# Sub_B_PCB.net
KiCad netlist of a schematic drawn in Altium Designer
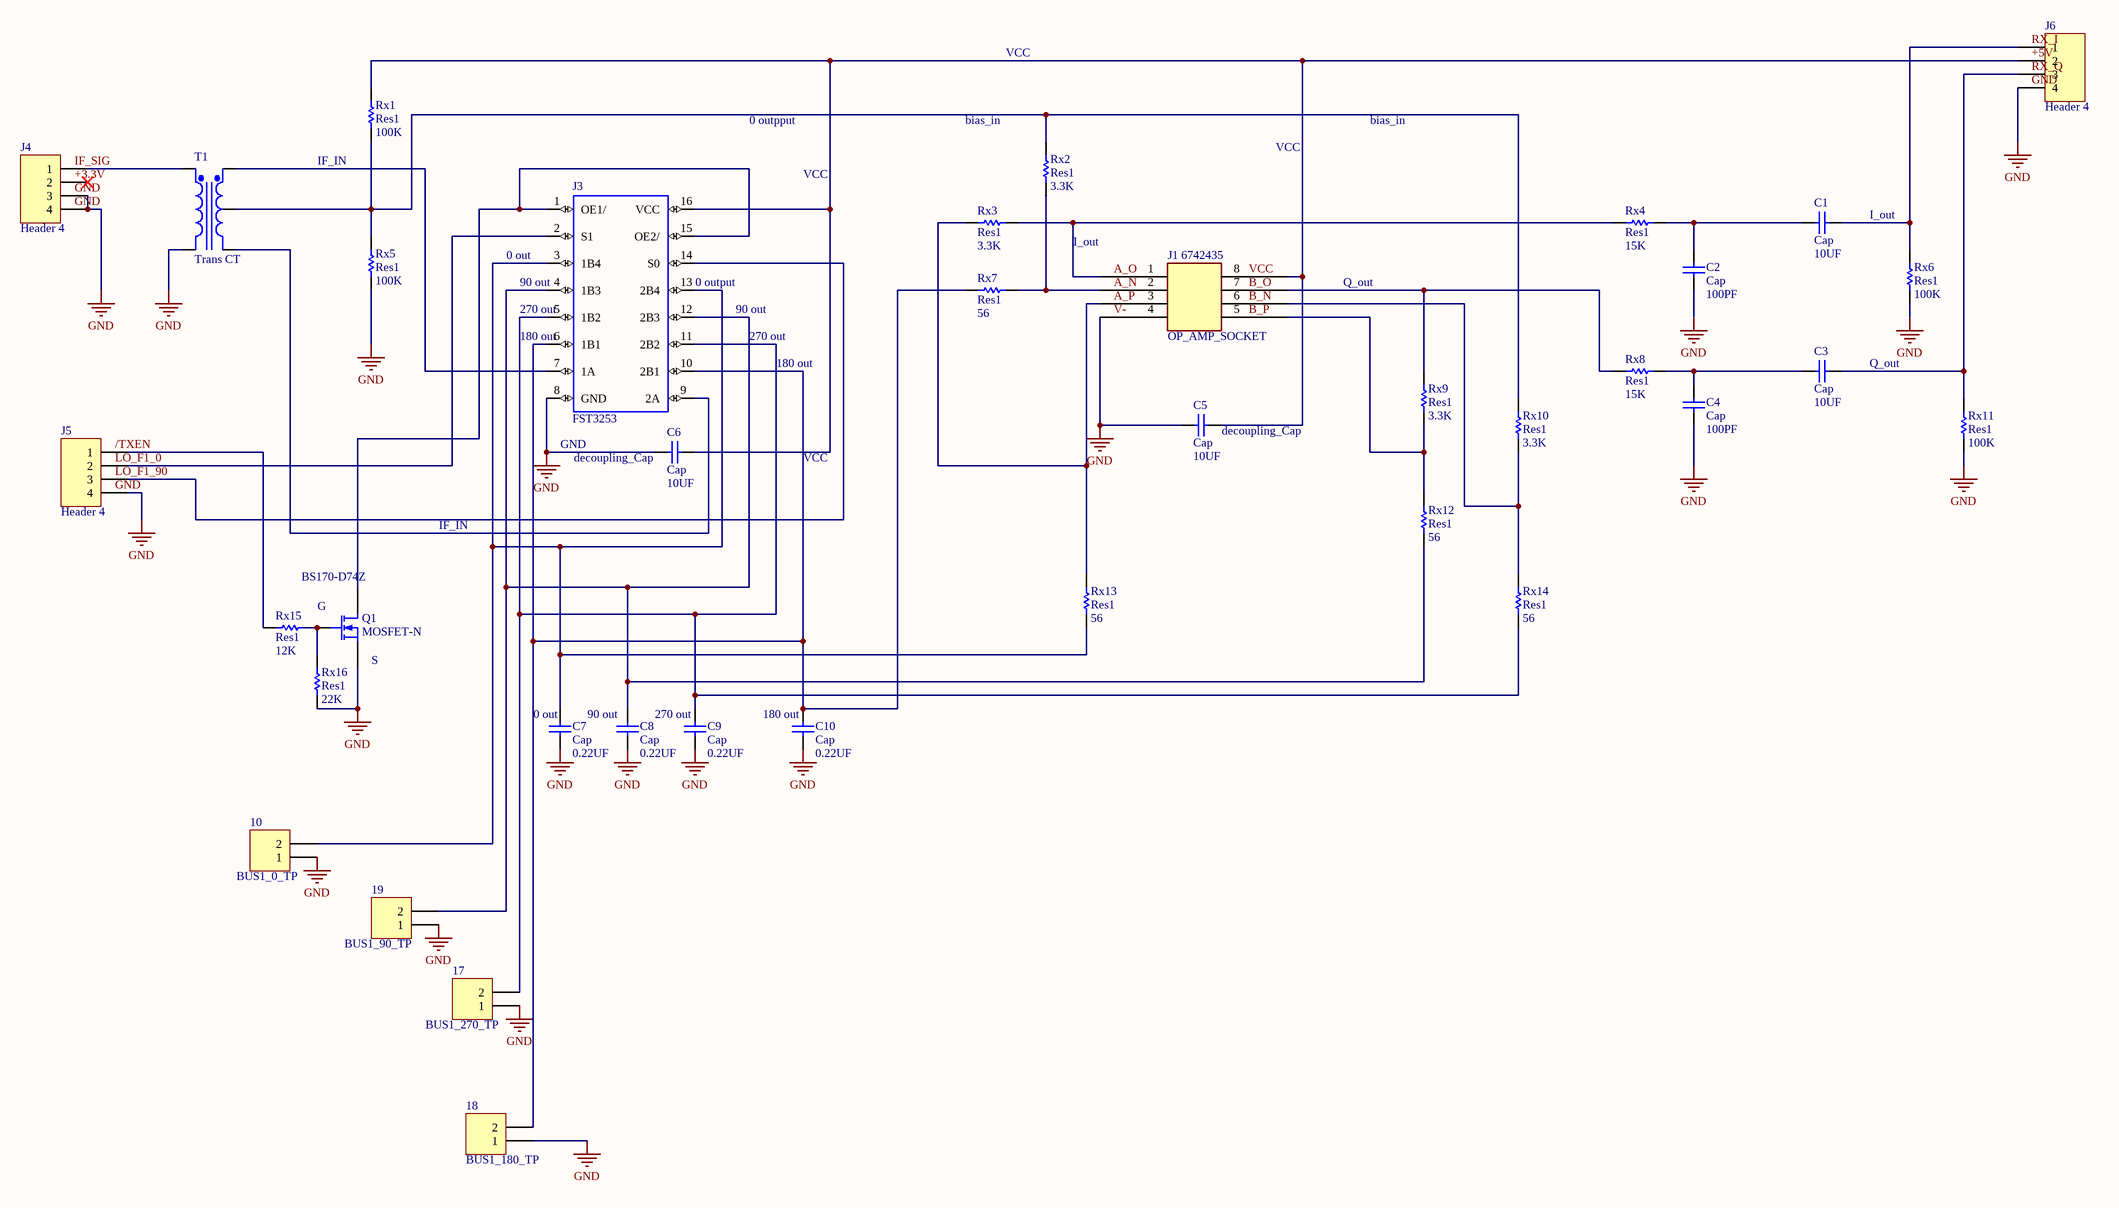
[diagram p0: Sub_B_PCB.SchDoc]

(export (version "E")
  (design (tool "Eeschema 10.0.6"))
  (components
    (comp (ref "10")
      (value "BUS1_0_TP")
      (footprint "HDR1X2")
      (description "Header, 2-Pin")
      (fields (field (name "PUBLISHER") "Altium Limited"))
      (libsource (lib "Miscellaneous Connectors") (part "Header 2"))
    )
    (comp (ref "17")
      (value "BUS1_270_TP")
      (footprint "HDR1X2")
      (description "Header, 2-Pin")
      (fields (field (name "PUBLISHER") "Altium Limited"))
      (libsource (lib "Miscellaneous Connectors") (part "Header 2"))
    )
    (comp (ref "18")
      (value "BUS1_180_TP")
      (footprint "HDR1X2")
      (description "Header, 2-Pin")
      (fields (field (name "PUBLISHER") "Altium Limited"))
      (libsource (lib "Miscellaneous Connectors") (part "Header 2"))
    )
    (comp (ref "19")
      (value "BUS1_90_TP")
      (footprint "HDR1X2")
      (description "Header, 2-Pin")
      (fields (field (name "PUBLISHER") "Altium Limited"))
      (libsource (lib "Miscellaneous Connectors") (part "Header 2"))
    )
    (comp (ref "C1")
      (value "Cap")
      (footprint "1206")
      (description "Capacitor")
      (fields
        (field (name "ALTIUM_VALUE") "10UF")
        (field (name "MANUFACTURER PART NUMBER") "885012108017")
        (field (name "PUBLISHER") "Altium Limited")
      )
      (libsource (lib "ECE295-Capacitors-SMT") (part "CAP CER 10UF 16V X5R 1206"))
    )
    (comp (ref "C2")
      (value "Cap")
      (footprint "RADIAL-0.1")
      (description "Capacitor")
      (fields
        (field (name "ALTIUM_VALUE") "100PF")
        (field (name "MANUFACTURER PART NUMBER") "K101K15C0GF53L2")
        (field (name "PUBLISHER") "Altium Limited")
      )
      (libsource (lib "ECE295-Capacitors-TH") (part "CAP CER 100PF 50V C0G/NP0 RADIAL"))
    )
    (comp (ref "C3")
      (value "Cap")
      (footprint "1206")
      (description "Capacitor")
      (fields
        (field (name "ALTIUM_VALUE") "10UF")
        (field (name "MANUFACTURER PART NUMBER") "885012108017")
        (field (name "PUBLISHER") "Altium Limited")
      )
      (libsource (lib "ECE295-Capacitors-SMT") (part "CAP CER 10UF 16V X5R 1206"))
    )
    (comp (ref "C4")
      (value "Cap")
      (footprint "RADIAL-0.1")
      (description "Capacitor")
      (fields
        (field (name "ALTIUM_VALUE") "100PF")
        (field (name "MANUFACTURER PART NUMBER") "K101K15C0GF53L2")
        (field (name "PUBLISHER") "Altium Limited")
      )
      (libsource (lib "ECE295-Capacitors-TH") (part "CAP CER 100PF 50V C0G/NP0 RADIAL"))
    )
    (comp (ref "C5")
      (value "Cap")
      (footprint "1206")
      (description "Capacitor")
      (fields
        (field (name "ALTIUM_VALUE") "10UF")
        (field (name "MANUFACTURER PART NUMBER") "885012108017")
        (field (name "PUBLISHER") "Altium Limited")
      )
      (libsource (lib "ECE295-Capacitors-SMT") (part "CAP CER 10UF 16V X5R 1206"))
    )
    (comp (ref "C6")
      (value "Cap")
      (footprint "1206")
      (description "Capacitor")
      (fields
        (field (name "ALTIUM_VALUE") "10UF")
        (field (name "MANUFACTURER PART NUMBER") "885012108017")
        (field (name "PUBLISHER") "Altium Limited")
      )
      (libsource (lib "ECE295-Capacitors-SMT") (part "CAP CER 10UF 16V X5R 1206"))
    )
    (comp (ref "C7")
      (value "Cap")
      (footprint "RADIAL-0.1")
      (description "Capacitor")
      (fields
        (field (name "ALTIUM_VALUE") "0.22UF")
        (field (name "MANUFACTURER PART NUMBER") "C320C224M5U5TA")
        (field (name "PUBLISHER") "Altium Limited")
      )
      (libsource (lib "ECE295-Capacitors-TH") (part "CAP CER 0.22UF 50V Z5U RADIAL"))
    )
    (comp (ref "C8")
      (value "Cap")
      (footprint "RADIAL-0.1")
      (description "Capacitor")
      (fields
        (field (name "ALTIUM_VALUE") "0.22UF")
        (field (name "MANUFACTURER PART NUMBER") "C320C224M5U5TA")
        (field (name "PUBLISHER") "Altium Limited")
      )
      (libsource (lib "ECE295-Capacitors-TH") (part "CAP CER 0.22UF 50V Z5U RADIAL"))
    )
    (comp (ref "C9")
      (value "Cap")
      (footprint "RADIAL-0.1")
      (description "Capacitor")
      (fields
        (field (name "ALTIUM_VALUE") "0.22UF")
        (field (name "MANUFACTURER PART NUMBER") "C320C224M5U5TA")
        (field (name "PUBLISHER") "Altium Limited")
      )
      (libsource (lib "ECE295-Capacitors-TH") (part "CAP CER 0.22UF 50V Z5U RADIAL"))
    )
    (comp (ref "C10")
      (value "Cap")
      (footprint "RADIAL-0.1")
      (description "Capacitor")
      (fields
        (field (name "ALTIUM_VALUE") "0.22UF")
        (field (name "MANUFACTURER PART NUMBER") "C320C224M5U5TA")
        (field (name "PUBLISHER") "Altium Limited")
      )
      (libsource (lib "ECE295-Capacitors-TH") (part "CAP CER 0.22UF 50V Z5U RADIAL"))
    )
    (comp (ref "J1")
      (value "OP_AMP_SOCKET")
      (footprint "TE_1-2199298-2")
      (description "8 _2 x 4_ Pos DIP, 0.3 _7.62mm_ Row Spacing Socket Tin Through Hole")
      (fields
        (field (name "MF") "TE Connectivity")
        (field (name "MP") "1-2199298-2")
        (field (name "SUPPLIER PART NUMBER 2") "6742435")
      )
      (libsource (lib "1-2199298-2") (part "1-2199298-2"))
    )
    (comp (ref "J3")
      (value "FST3253")
      (footprint "SOIC127P600X175-16N")
      (description "Multiplekser/demultiplekser 2 x 4:1 16-TSSOP")
      (fields (field (name "MF") "ON Semiconductor"))
      (libsource (lib "FST3253") (part "FST3253"))
    )
    (comp (ref "J4")
      (value "Header 4")
      (footprint "HDR1X4")
      (description "Header, 4-Pin")
      (fields (field (name "PUBLISHER") "Altium Limited"))
      (libsource (lib "") (part "Header 4_1"))
    )
    (comp (ref "J5")
      (value "Header 4")
      (footprint "HDR1X4")
      (description "Header, 4-Pin")
      (fields (field (name "PUBLISHER") "Altium Limited"))
      (libsource (lib "") (part "Header 4_1"))
    )
    (comp (ref "J6")
      (value "Header 4")
      (footprint "HDR1X4")
      (description "Header, 4-Pin")
      (fields (field (name "PUBLISHER") "Altium Limited"))
      (libsource (lib "Miscellaneous Connectors") (part "Header 4"))
    )
    (comp (ref "Q1")
      (value "MOSFET-N")
      (footprint "E3")
      (description "N-Channel MOSFET")
      (fields
        (field (name "SUPPLIER PART NUMBER 1") "BS170-D74Z")
        (field (name "PUBLISHER") "Altium Limited")
      )
      (libsource (lib "Miscellaneous Devices") (part "MOSFET-N"))
    )
    (comp (ref "Rx1")
      (value "Res1")
      (footprint "AXIAL-0.1-RES")
      (description "Resistor")
      (fields
        (field (name "ALTIUM_VALUE") "100K")
        (field (name "MANUFACTURER PART NUMBER") "CFR-25JB-52-100K")
        (field (name "TOLERANCE") "0.05")
        (field (name "PUBLISHER") "Altium Limited")
      )
      (libsource (lib "ECE295-Resistors-TH") (part "RES 100K OHM 5% 1/4W AXIAL"))
    )
    (comp (ref "Rx2")
      (value "Res1")
      (footprint "AXIAL-0.1-RES")
      (description "Resistor")
      (fields
        (field (name "ALTIUM_VALUE") "3.3K")
        (field (name "MANUFACTURER PART NUMBER") "CFR-25JB-52-3K3")
        (field (name "TOLERANCE") "0.05")
        (field (name "PUBLISHER") "Altium Limited")
      )
      (libsource (lib "ECE295-Resistors-TH") (part "RES 3.3K OHM 5% 1/4W AXIAL"))
    )
    (comp (ref "Rx3")
      (value "Res1")
      (footprint "AXIAL-0.1-RES")
      (description "Resistor")
      (fields
        (field (name "ALTIUM_VALUE") "3.3K")
        (field (name "MANUFACTURER PART NUMBER") "CFR-25JB-52-3K3")
        (field (name "TOLERANCE") "0.05")
        (field (name "PUBLISHER") "Altium Limited")
      )
      (libsource (lib "ECE295-Resistors-TH") (part "RES 3.3K OHM 5% 1/4W AXIAL"))
    )
    (comp (ref "Rx4")
      (value "Res1")
      (footprint "AXIAL-0.1-RES")
      (description "Resistor")
      (fields
        (field (name "ALTIUM_VALUE") "15K")
        (field (name "MANUFACTURER PART NUMBER") "CFR-25JB-52-15K")
        (field (name "TOLERANCE") "0.05")
        (field (name "PUBLISHER") "Altium Limited")
      )
      (libsource (lib "ECE295-Resistors-TH") (part "RES 15K OHM 5% 1/4W AXIAL"))
    )
    (comp (ref "Rx5")
      (value "Res1")
      (footprint "AXIAL-0.1-RES")
      (description "Resistor")
      (fields
        (field (name "ALTIUM_VALUE") "100K")
        (field (name "MANUFACTURER PART NUMBER") "CFR-25JB-52-100K")
        (field (name "TOLERANCE") "0.05")
        (field (name "PUBLISHER") "Altium Limited")
      )
      (libsource (lib "ECE295-Resistors-TH") (part "RES 100K OHM 5% 1/4W AXIAL"))
    )
    (comp (ref "Rx6")
      (value "Res1")
      (footprint "AXIAL-0.1-RES")
      (description "Resistor")
      (fields
        (field (name "ALTIUM_VALUE") "100K")
        (field (name "MANUFACTURER PART NUMBER") "CFR-25JB-52-100K")
        (field (name "TOLERANCE") "0.05")
        (field (name "PUBLISHER") "Altium Limited")
      )
      (libsource (lib "ECE295-Resistors-TH") (part "RES 100K OHM 5% 1/4W AXIAL"))
    )
    (comp (ref "Rx7")
      (value "Res1")
      (footprint "AXIAL-0.1-RES")
      (description "Resistor")
      (fields
        (field (name "ALTIUM_VALUE") "56")
        (field (name "MANUFACTURER PART NUMBER") "CFR-25JB-52-56R")
        (field (name "TOLERANCE") "0.05")
        (field (name "PUBLISHER") "Altium Limited")
      )
      (libsource (lib "ECE295-Resistors-TH") (part "RES 56 OHM 5% 1/4W AXIAL"))
    )
    (comp (ref "Rx8")
      (value "Res1")
      (footprint "AXIAL-0.1-RES")
      (description "Resistor")
      (fields
        (field (name "ALTIUM_VALUE") "15K")
        (field (name "MANUFACTURER PART NUMBER") "CFR-25JB-52-15K")
        (field (name "TOLERANCE") "0.05")
        (field (name "PUBLISHER") "Altium Limited")
      )
      (libsource (lib "ECE295-Resistors-TH") (part "RES 15K OHM 5% 1/4W AXIAL"))
    )
    (comp (ref "Rx9")
      (value "Res1")
      (footprint "AXIAL-0.1-RES")
      (description "Resistor")
      (fields
        (field (name "ALTIUM_VALUE") "3.3K")
        (field (name "MANUFACTURER PART NUMBER") "CFR-25JB-52-3K3")
        (field (name "TOLERANCE") "0.05")
        (field (name "PUBLISHER") "Altium Limited")
      )
      (libsource (lib "ECE295-Resistors-TH") (part "RES 3.3K OHM 5% 1/4W AXIAL"))
    )
    (comp (ref "Rx10")
      (value "Res1")
      (footprint "AXIAL-0.1-RES")
      (description "Resistor")
      (fields
        (field (name "ALTIUM_VALUE") "3.3K")
        (field (name "MANUFACTURER PART NUMBER") "CFR-25JB-52-3K3")
        (field (name "TOLERANCE") "0.05")
        (field (name "PUBLISHER") "Altium Limited")
      )
      (libsource (lib "ECE295-Resistors-TH") (part "RES 3.3K OHM 5% 1/4W AXIAL"))
    )
    (comp (ref "Rx11")
      (value "Res1")
      (footprint "AXIAL-0.1-RES")
      (description "Resistor")
      (fields
        (field (name "ALTIUM_VALUE") "100K")
        (field (name "MANUFACTURER PART NUMBER") "CFR-25JB-52-100K")
        (field (name "TOLERANCE") "0.05")
        (field (name "PUBLISHER") "Altium Limited")
      )
      (libsource (lib "ECE295-Resistors-TH") (part "RES 100K OHM 5% 1/4W AXIAL"))
    )
    (comp (ref "Rx12")
      (value "Res1")
      (footprint "AXIAL-0.1-RES")
      (description "Resistor")
      (fields
        (field (name "ALTIUM_VALUE") "56")
        (field (name "MANUFACTURER PART NUMBER") "CFR-25JB-52-56R")
        (field (name "TOLERANCE") "0.05")
        (field (name "PUBLISHER") "Altium Limited")
      )
      (libsource (lib "ECE295-Resistors-TH") (part "RES 56 OHM 5% 1/4W AXIAL"))
    )
    (comp (ref "Rx13")
      (value "Res1")
      (footprint "AXIAL-0.1-RES")
      (description "Resistor")
      (fields
        (field (name "ALTIUM_VALUE") "56")
        (field (name "MANUFACTURER PART NUMBER") "CFR-25JB-52-56R")
        (field (name "TOLERANCE") "0.05")
        (field (name "PUBLISHER") "Altium Limited")
      )
      (libsource (lib "ECE295-Resistors-TH") (part "RES 56 OHM 5% 1/4W AXIAL"))
    )
    (comp (ref "Rx14")
      (value "Res1")
      (footprint "AXIAL-0.1-RES")
      (description "Resistor")
      (fields
        (field (name "ALTIUM_VALUE") "56")
        (field (name "MANUFACTURER PART NUMBER") "CFR-25JB-52-56R")
        (field (name "TOLERANCE") "0.05")
        (field (name "PUBLISHER") "Altium Limited")
      )
      (libsource (lib "ECE295-Resistors-TH") (part "RES 56 OHM 5% 1/4W AXIAL"))
    )
    (comp (ref "Rx15")
      (value "Res1")
      (footprint "AXIAL-0.1-RES")
      (description "Resistor")
      (fields
        (field (name "ALTIUM_VALUE") "12K")
        (field (name "MANUFACTURER PART NUMBER") "CFR-25JB-52-12K")
        (field (name "TOLERANCE") "0.05")
        (field (name "PUBLISHER") "Altium Limited")
      )
      (libsource (lib "ECE295-Resistors-TH") (part "RES 12K OHM 5% 1/4W AXIAL"))
    )
    (comp (ref "Rx16")
      (value "Res1")
      (footprint "AXIAL-0.1-RES")
      (description "Resistor")
      (fields
        (field (name "ALTIUM_VALUE") "22K")
        (field (name "MANUFACTURER PART NUMBER") "CFR-25JB-52-22K")
        (field (name "TOLERANCE") "0.05")
        (field (name "PUBLISHER") "Altium Limited")
      )
      (libsource (lib "ECE295-Resistors-TH") (part "RES 22K OHM 5% 1/4W AXIAL"))
    )
    (comp (ref "T1")
      (value "Trans CT")
      (footprint "BIFILAR-2402")
      (description "Center-Tapped Transformer (Coupled Inductor Model)")
      (fields (field (name "PUBLISHER") "Altium Limited"))
      (libsource (lib "ECE295-Other") (part "Centre-tapped transformer wound on a binocular core"))
    )
  )
  (nets
    (net (code "17") (name "GND") (class "Default")
      (node (ref "10") (pin "1") (pinfunction "1_1") (pintype "passive"))
      (node (ref "17") (pin "1") (pinfunction "1_1") (pintype "passive"))
      (node (ref "18") (pin "1") (pinfunction "1_1") (pintype "passive"))
      (node (ref "19") (pin "1") (pinfunction "1_1") (pintype "passive"))
      (node (ref "C10") (pin "1") (pinfunction "1_1") (pintype "passive"))
      (node (ref "C2") (pin "1") (pinfunction "1_1") (pintype "passive"))
      (node (ref "C4") (pin "1") (pinfunction "1_1") (pintype "passive"))
      (node (ref "C5") (pin "1") (pinfunction "1_1") (pintype "passive"))
      (node (ref "C6") (pin "1") (pinfunction "1_1") (pintype "passive"))
      (node (ref "C7") (pin "1") (pinfunction "1_1") (pintype "passive"))
      (node (ref "C8") (pin "1") (pinfunction "1_1") (pintype "passive"))
      (node (ref "C9") (pin "1") (pinfunction "1_1") (pintype "passive"))
      (node (ref "J1") (pin "4") (pinfunction "V-_4") (pintype "passive"))
      (node (ref "J3") (pin "8") (pinfunction "GND_8") (pintype "bidirectional"))
      (node (ref "J4") (pin "3") (pinfunction "3_3") (pintype "passive"))
      (node (ref "J4") (pin "4") (pinfunction "4_4") (pintype "passive"))
      (node (ref "J5") (pin "4") (pinfunction "4_4") (pintype "passive"))
      (node (ref "J6") (pin "4") (pinfunction "4_4") (pintype "passive"))
      (node (ref "Q1") (pin "3") (pinfunction "S_3") (pintype "passive"))
      (node (ref "Rx11") (pin "1") (pinfunction "1_1") (pintype "passive"))
      (node (ref "Rx16") (pin "1") (pinfunction "1_1") (pintype "passive"))
      (node (ref "Rx5") (pin "1") (pinfunction "1_1") (pintype "passive"))
      (node (ref "Rx6") (pin "1") (pinfunction "1_1") (pintype "passive"))
      (node (ref "T1") (pin "5") (pinfunction "Pri-_5") (pintype "passive"))
    )
    (net (code "18") (name "Net-(C1-Pad1)") (class "Default")
      (node (ref "C1") (pin "1") (pinfunction "1_1") (pintype "passive"))
      (node (ref "C2") (pin "2") (pinfunction "2_2") (pintype "passive"))
      (node (ref "Rx4") (pin "2") (pinfunction "2_2") (pintype "passive"))
    )
    (net (code "19") (name "Net-(C1-Pad2)") (class "Default")
      (node (ref "C1") (pin "2") (pinfunction "2_2") (pintype "passive"))
      (node (ref "J6") (pin "1") (pinfunction "1_1") (pintype "passive"))
      (node (ref "Rx6") (pin "2") (pinfunction "2_2") (pintype "passive"))
    )
    (net (code "20") (name "Net-(C3-Pad1)") (class "Default")
      (node (ref "C3") (pin "1") (pinfunction "1_1") (pintype "passive"))
      (node (ref "C4") (pin "2") (pinfunction "2_2") (pintype "passive"))
      (node (ref "Rx8") (pin "2") (pinfunction "2_2") (pintype "passive"))
    )
    (net (code "21") (name "Net-(C3-Pad2)") (class "Default")
      (node (ref "C3") (pin "2") (pinfunction "2_2") (pintype "passive"))
      (node (ref "J6") (pin "3") (pinfunction "3_3") (pintype "passive"))
      (node (ref "Rx11") (pin "2") (pinfunction "2_2") (pintype "passive"))
    )
    (net (code "22") (name "Net-(J1-INVERTING_A)") (class "Default")
      (node (ref "J1") (pin "2") (pinfunction "INVERTING_A_2") (pintype "passive"))
      (node (ref "Rx2") (pin "1") (pinfunction "1_1") (pintype "passive"))
      (node (ref "Rx7") (pin "2") (pinfunction "2_2") (pintype "passive"))
    )
    (net (code "23") (name "Net-(J1-INVERTING_B)") (class "Default")
      (node (ref "J1") (pin "6") (pinfunction "INVERTING_B_6") (pintype "passive"))
      (node (ref "Rx10") (pin "1") (pinfunction "1_1") (pintype "passive"))
      (node (ref "Rx14") (pin "2") (pinfunction "2_2") (pintype "passive"))
    )
    (net (code "24") (name "Net-(J1-NON-INVERTING_A)") (class "Default")
      (node (ref "J1") (pin "3") (pinfunction "NON-INVERTING_A_3") (pintype "passive"))
      (node (ref "Rx13") (pin "2") (pinfunction "2_2") (pintype "passive"))
      (node (ref "Rx3") (pin "1") (pinfunction "1_1") (pintype "passive"))
    )
    (net (code "25") (name "Net-(J1-NON-INVERTING_B)") (class "Default")
      (node (ref "J1") (pin "5") (pinfunction "NON-INVERTING_B_5") (pintype "passive"))
      (node (ref "Rx12") (pin "2") (pinfunction "2_2") (pintype "passive"))
      (node (ref "Rx9") (pin "1") (pinfunction "1_1") (pintype "passive"))
    )
    (net (code "26") (name "Net-(J1-OOUTPUT__A)") (class "Default")
      (node (ref "J1") (pin "1") (pinfunction "OOUTPUT__A_1") (pintype "passive"))
      (node (ref "Rx3") (pin "2") (pinfunction "2_2") (pintype "passive"))
      (node (ref "Rx4") (pin "1") (pinfunction "1_1") (pintype "passive"))
    )
    (net (code "27") (name "Net-(J1-OUTPUT_B)") (class "Default")
      (node (ref "J1") (pin "7") (pinfunction "OUTPUT_B_7") (pintype "passive"))
      (node (ref "Rx8") (pin "1") (pinfunction "1_1") (pintype "passive"))
      (node (ref "Rx9") (pin "2") (pinfunction "2_2") (pintype "passive"))
    )
    (net (code "28") (name "Net-(J1-VCC)") (class "Default")
      (node (ref "C5") (pin "2") (pinfunction "2_2") (pintype "passive"))
      (node (ref "C6") (pin "2") (pinfunction "2_2") (pintype "passive"))
      (node (ref "J1") (pin "8") (pinfunction "VCC_8") (pintype "passive"))
      (node (ref "J3") (pin "16") (pinfunction "VCC_16") (pintype "bidirectional"))
      (node (ref "J6") (pin "2") (pinfunction "2_2") (pintype "passive"))
      (node (ref "Rx1") (pin "2") (pinfunction "2_2") (pintype "passive"))
    )
    (net (code "29") (name "Net-(J3-1A)") (class "Default")
      (node (ref "J3") (pin "7") (pinfunction "1A_7") (pintype "bidirectional"))
      (node (ref "T1") (pin "1") (pinfunction "Sec+_1") (pintype "passive"))
    )
    (net (code "30") (name "Net-(J3-1B1)") (class "Default")
      (node (ref "18") (pin "2") (pinfunction "2_2") (pintype "passive"))
      (node (ref "C10") (pin "2") (pinfunction "2_2") (pintype "passive"))
      (node (ref "J3") (pin "10") (pinfunction "2B1_10") (pintype "bidirectional"))
      (node (ref "J3") (pin "6") (pinfunction "1B1_6") (pintype "bidirectional"))
      (node (ref "Rx7") (pin "1") (pinfunction "1_1") (pintype "passive"))
    )
    (net (code "31") (name "Net-(J3-1B2)") (class "Default")
      (node (ref "17") (pin "2") (pinfunction "2_2") (pintype "passive"))
      (node (ref "C9") (pin "2") (pinfunction "2_2") (pintype "passive"))
      (node (ref "J3") (pin "11") (pinfunction "2B2_11") (pintype "bidirectional"))
      (node (ref "J3") (pin "5") (pinfunction "1B2_5") (pintype "bidirectional"))
      (node (ref "Rx14") (pin "1") (pinfunction "1_1") (pintype "passive"))
    )
    (net (code "32") (name "Net-(J3-1B3)") (class "Default")
      (node (ref "19") (pin "2") (pinfunction "2_2") (pintype "passive"))
      (node (ref "C8") (pin "2") (pinfunction "2_2") (pintype "passive"))
      (node (ref "J3") (pin "12") (pinfunction "2B3_12") (pintype "bidirectional"))
      (node (ref "J3") (pin "4") (pinfunction "1B3_4") (pintype "bidirectional"))
      (node (ref "Rx12") (pin "1") (pinfunction "1_1") (pintype "passive"))
    )
    (net (code "33") (name "Net-(J3-1B4)") (class "Default")
      (node (ref "10") (pin "2") (pinfunction "2_2") (pintype "passive"))
      (node (ref "C7") (pin "2") (pinfunction "2_2") (pintype "passive"))
      (node (ref "J3") (pin "13") (pinfunction "2B4_13") (pintype "bidirectional"))
      (node (ref "J3") (pin "3") (pinfunction "1B4_3") (pintype "bidirectional"))
      (node (ref "Rx13") (pin "1") (pinfunction "1_1") (pintype "passive"))
    )
    (net (code "34") (name "Net-(J3-2A)") (class "Default")
      (node (ref "J3") (pin "9") (pinfunction "2A_9") (pintype "bidirectional"))
      (node (ref "T1") (pin "3") (pinfunction "Sec-_3") (pintype "passive"))
    )
    (net (code "35") (name "Net-(J3-OE1{slash})") (class "Default")
      (node (ref "J3") (pin "1") (pinfunction "OE1/_1") (pintype "bidirectional"))
      (node (ref "J3") (pin "15") (pinfunction "OE2/_15") (pintype "bidirectional"))
      (node (ref "Q1") (pin "1") (pinfunction "D_1") (pintype "passive"))
    )
    (net (code "36") (name "Net-(J3-S0)") (class "Default")
      (node (ref "J3") (pin "14") (pinfunction "S0_14") (pintype "bidirectional"))
      (node (ref "J5") (pin "3") (pinfunction "3_3") (pintype "passive"))
    )
    (net (code "37") (name "Net-(J3-S1)") (class "Default")
      (node (ref "J3") (pin "2") (pinfunction "S1_2") (pintype "bidirectional"))
      (node (ref "J5") (pin "2") (pinfunction "2_2") (pintype "passive"))
    )
    (net (code "38") (name "Net-(J5-Pad1)") (class "Default")
      (node (ref "J5") (pin "1") (pinfunction "1_1") (pintype "passive"))
      (node (ref "Rx15") (pin "1") (pinfunction "1_1") (pintype "passive"))
    )
    (net (code "39") (name "Net-(Q1-G)") (class "Default")
      (node (ref "Q1") (pin "2") (pinfunction "G_2") (pintype "passive"))
      (node (ref "Rx15") (pin "2") (pinfunction "2_2") (pintype "passive"))
      (node (ref "Rx16") (pin "2") (pinfunction "2_2") (pintype "passive"))
    )
    (net (code "40") (name "Net-(T1-Pri+)") (class "Default")
      (node (ref "J4") (pin "1") (pinfunction "1_1") (pintype "passive"))
      (node (ref "T1") (pin "4") (pinfunction "Pri+_4") (pintype "passive"))
    )
    (net (code "41") (name "Net-(T1-SecCT)") (class "Default")
      (node (ref "Rx1") (pin "1") (pinfunction "1_1") (pintype "passive"))
      (node (ref "Rx10") (pin "2") (pinfunction "2_2") (pintype "passive"))
      (node (ref "Rx2") (pin "2") (pinfunction "2_2") (pintype "passive"))
      (node (ref "Rx5") (pin "2") (pinfunction "2_2") (pintype "passive"))
      (node (ref "T1") (pin "2") (pinfunction "SecCT_2") (pintype "passive"))
    )
    (net (code "42") (name "unconnected-(J4-Pad2)") (class "Default")
      (node (ref "J4") (pin "2") (pinfunction "2_2") (pintype "passive+no_connect"))
    )
  )
)
